# bottom_board_v6.net
KiCad netlist of a schematic drawn in EAGLE
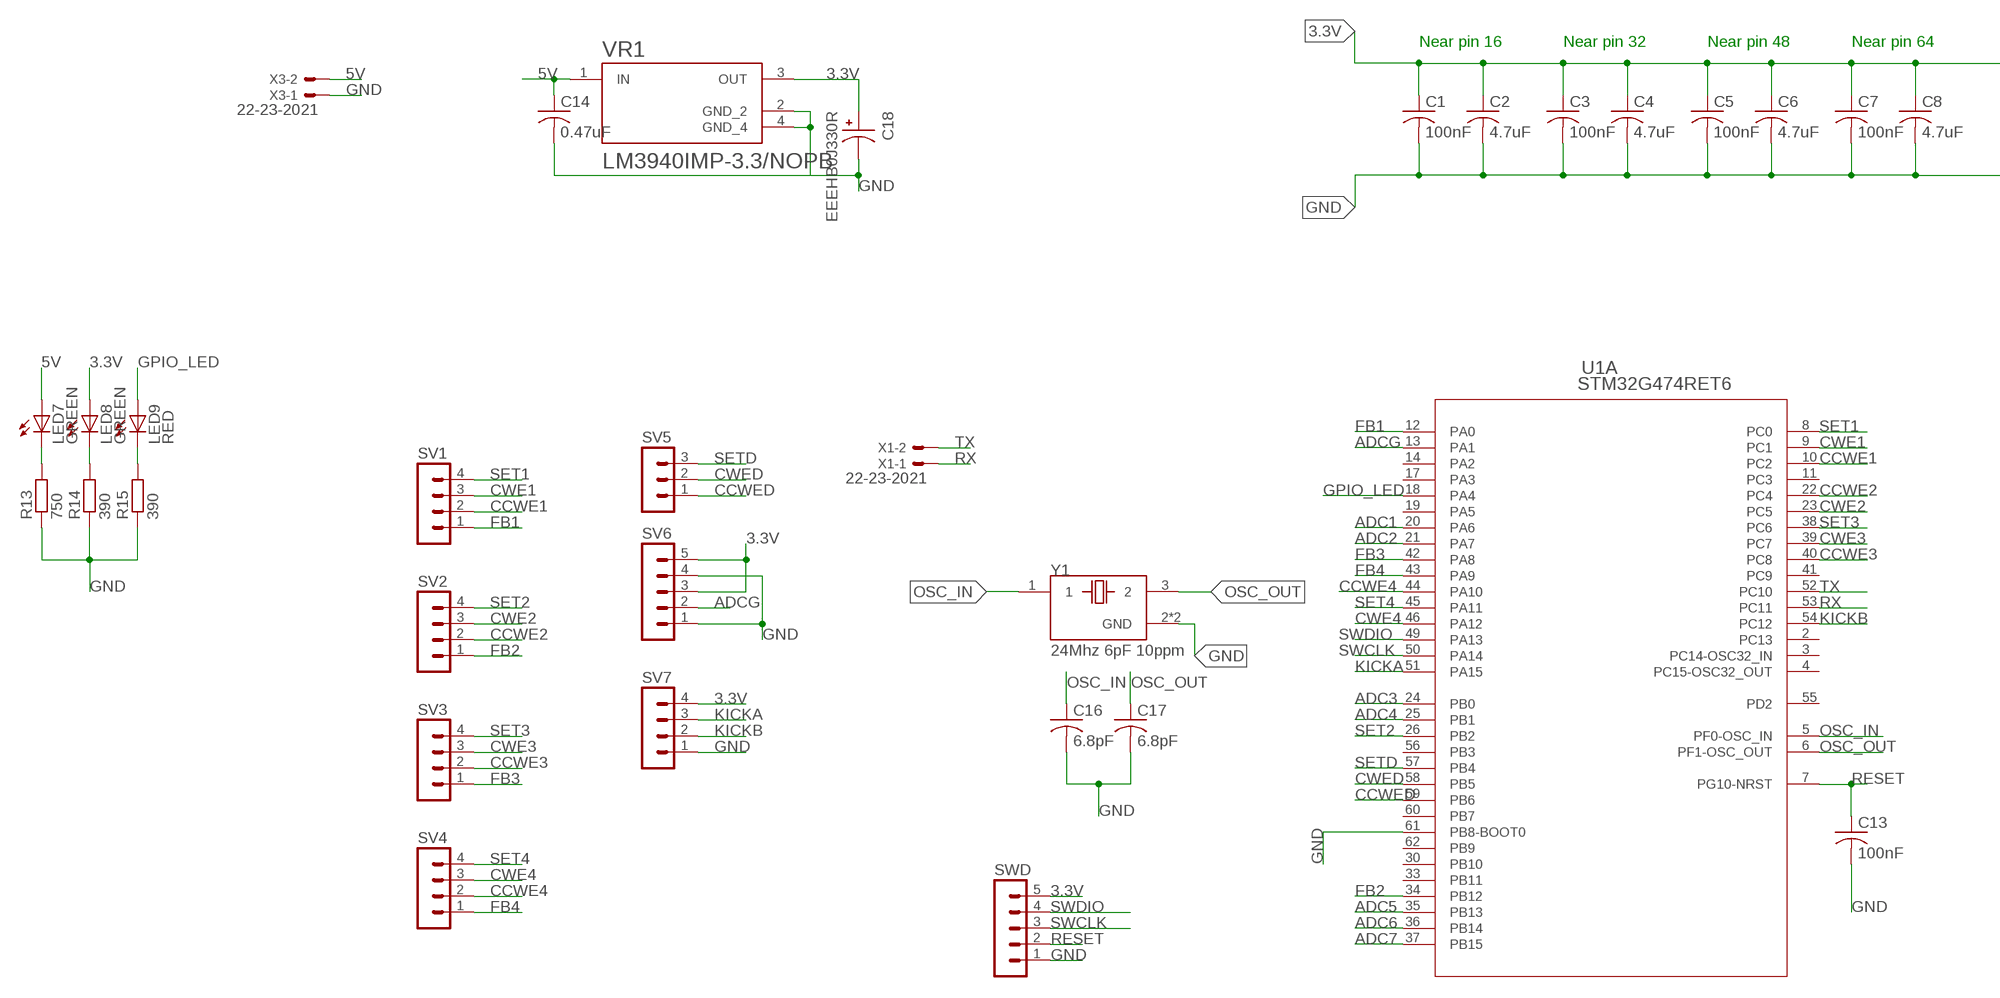
[diagram p0: schematic, sheet 1, part 1 of 2]
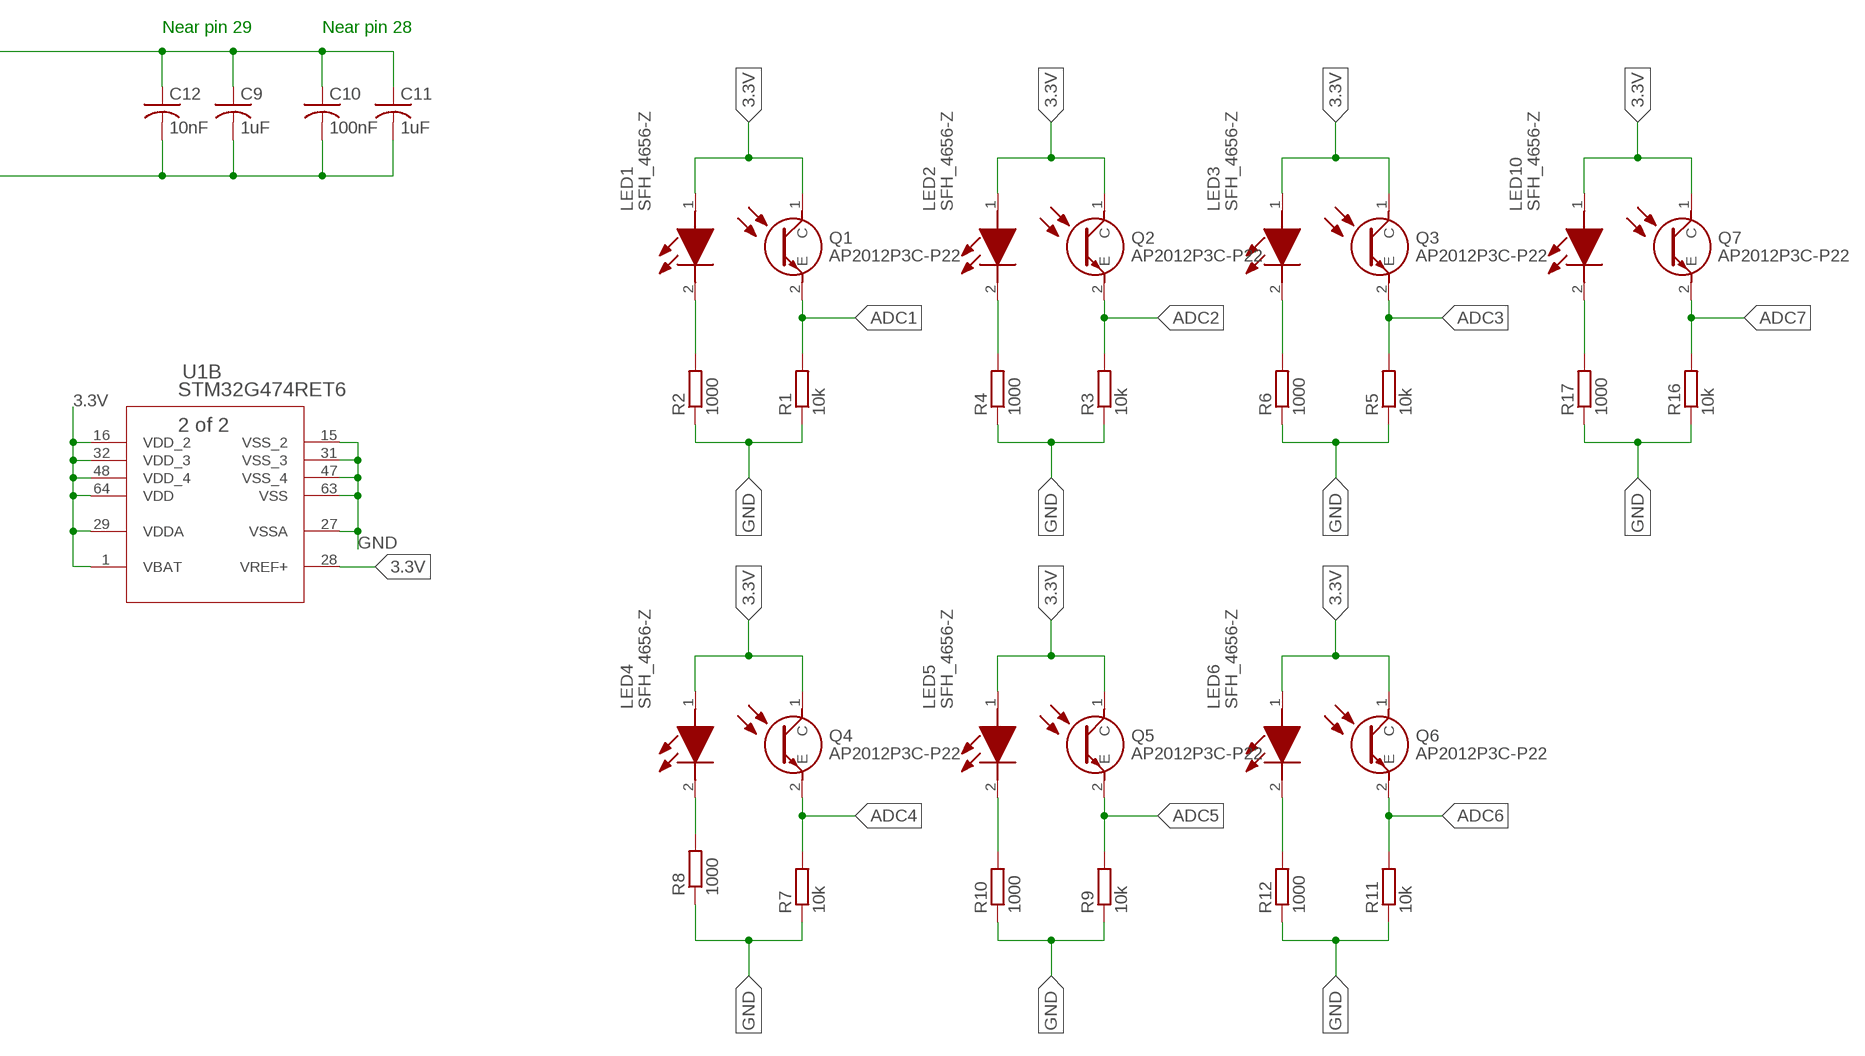
[diagram p1: schematic, sheet 1, part 2 of 2]

(export (version "E")
  (design (tool "Eeschema 10.0.6"))
  (components
    (comp (ref "C1")
      (value "100nF")
      (footprint "eagle-import:C0603")
      (libsource (lib "eagle-import") (part "C-USC0603"))
    )
    (comp (ref "C2")
      (value "4.7uF")
      (footprint "eagle-import:C0603")
      (libsource (lib "eagle-import") (part "C-USC0603"))
    )
    (comp (ref "C3")
      (value "100nF")
      (footprint "eagle-import:C0603")
      (libsource (lib "eagle-import") (part "C-USC0603"))
    )
    (comp (ref "C4")
      (value "4.7uF")
      (footprint "eagle-import:C0603")
      (libsource (lib "eagle-import") (part "C-USC0603"))
    )
    (comp (ref "C5")
      (value "100nF")
      (footprint "eagle-import:C0603")
      (libsource (lib "eagle-import") (part "C-USC0603"))
    )
    (comp (ref "C6")
      (value "4.7uF")
      (footprint "eagle-import:C0603")
      (libsource (lib "eagle-import") (part "C-USC0603"))
    )
    (comp (ref "C7")
      (value "100nF")
      (footprint "eagle-import:C0603")
      (libsource (lib "eagle-import") (part "C-USC0603"))
    )
    (comp (ref "C8")
      (value "4.7uF")
      (footprint "eagle-import:C0603")
      (libsource (lib "eagle-import") (part "C-USC0603"))
    )
    (comp (ref "C9")
      (value "1uF")
      (footprint "eagle-import:C0603")
      (libsource (lib "eagle-import") (part "C-USC0603"))
    )
    (comp (ref "C10")
      (value "100nF")
      (footprint "eagle-import:C0603")
      (libsource (lib "eagle-import") (part "C-USC0603"))
    )
    (comp (ref "C11")
      (value "1uF")
      (footprint "eagle-import:C0603")
      (libsource (lib "eagle-import") (part "C-USC0603"))
    )
    (comp (ref "C12")
      (value "10nF")
      (footprint "eagle-import:C0603")
      (libsource (lib "eagle-import") (part "C-USC0603"))
    )
    (comp (ref "C13")
      (value "100nF")
      (footprint "eagle-import:C0603")
      (libsource (lib "eagle-import") (part "C-USC0603"))
    )
    (comp (ref "C14")
      (value "0.47uF")
      (footprint "eagle-import:C0603")
      (libsource (lib "eagle-import") (part "C-USC0603"))
    )
    (comp (ref "C16")
      (value "6.8pF")
      (footprint "eagle-import:C0603")
      (libsource (lib "eagle-import") (part "C-USC0603"))
    )
    (comp (ref "C17")
      (value "6.8pF")
      (footprint "eagle-import:C0603")
      (libsource (lib "eagle-import") (part "C-USC0603"))
    )
    (comp (ref "C18")
      (value "EEEHB0J330R")
      (footprint "eagle-import:CAP_EEEHB0J330R")
      (fields (field (name "MF") "Panasonic") (field (name "MP") "EEE-HB0J330R"))
      (libsource (lib "eagle-import") (part "EEEHB0J330R"))
    )
    (comp (ref "LED1")
      (value "SFH_4656-Z")
      (footprint "eagle-import:SFH4656Z")
      (fields
        (field (name "MANUFACTURER_PART_NUMBER") "SFH 4656-Z")
        (field (name "MOUSER_PART_NUMBER") "720-SFH4656-Z")
      )
      (libsource (lib "eagle-import") (part "SFH_4656-Z"))
    )
    (comp (ref "LED2")
      (value "SFH_4656-Z")
      (footprint "eagle-import:SFH4656Z")
      (fields
        (field (name "MANUFACTURER_PART_NUMBER") "SFH 4656-Z")
        (field (name "MOUSER_PART_NUMBER") "720-SFH4656-Z")
      )
      (libsource (lib "eagle-import") (part "SFH_4656-Z"))
    )
    (comp (ref "LED3")
      (value "SFH_4656-Z")
      (footprint "eagle-import:SFH4656Z")
      (fields
        (field (name "MANUFACTURER_PART_NUMBER") "SFH 4656-Z")
        (field (name "MOUSER_PART_NUMBER") "720-SFH4656-Z")
      )
      (libsource (lib "eagle-import") (part "SFH_4656-Z"))
    )
    (comp (ref "LED4")
      (value "SFH_4656-Z")
      (footprint "eagle-import:SFH4656Z")
      (fields
        (field (name "MANUFACTURER_PART_NUMBER") "SFH 4656-Z")
        (field (name "MOUSER_PART_NUMBER") "720-SFH4656-Z")
      )
      (libsource (lib "eagle-import") (part "SFH_4656-Z"))
    )
    (comp (ref "LED5")
      (value "SFH_4656-Z")
      (footprint "eagle-import:SFH4656Z")
      (fields
        (field (name "MANUFACTURER_PART_NUMBER") "SFH 4656-Z")
        (field (name "MOUSER_PART_NUMBER") "720-SFH4656-Z")
      )
      (libsource (lib "eagle-import") (part "SFH_4656-Z"))
    )
    (comp (ref "LED6")
      (value "SFH_4656-Z")
      (footprint "eagle-import:SFH4656Z")
      (fields
        (field (name "MANUFACTURER_PART_NUMBER") "SFH 4656-Z")
        (field (name "MOUSER_PART_NUMBER") "720-SFH4656-Z")
      )
      (libsource (lib "eagle-import") (part "SFH_4656-Z"))
    )
    (comp (ref "LED7")
      (value "GREEN")
      (footprint "eagle-import:CHIPLED_0603")
      (libsource (lib "eagle-import") (part "LEDCHIPLED_0603"))
    )
    (comp (ref "LED8")
      (value "GREEN")
      (footprint "eagle-import:CHIPLED_0603")
      (libsource (lib "eagle-import") (part "LEDCHIPLED_0603"))
    )
    (comp (ref "LED9")
      (value "RED")
      (footprint "eagle-import:CHIPLED_0603")
      (libsource (lib "eagle-import") (part "LEDCHIPLED_0603"))
    )
    (comp (ref "LED10")
      (value "SFH_4656-Z")
      (footprint "eagle-import:SFH4656Z")
      (fields
        (field (name "MANUFACTURER_PART_NUMBER") "SFH 4656-Z")
        (field (name "MOUSER_PART_NUMBER") "720-SFH4656-Z")
      )
      (libsource (lib "eagle-import") (part "SFH_4656-Z"))
    )
    (comp (ref "Q1")
      (value "AP2012P3C-P22")
      (footprint "eagle-import:AP2012P3CP22")
      (fields (field (name "MOUSER_PART_NUMBER") "604-AP2012P3C-P22"))
      (libsource (lib "eagle-import") (part "AP2012P3C-P22"))
    )
    (comp (ref "Q2")
      (value "AP2012P3C-P22")
      (footprint "eagle-import:AP2012P3CP22")
      (fields (field (name "MOUSER_PART_NUMBER") "604-AP2012P3C-P22"))
      (libsource (lib "eagle-import") (part "AP2012P3C-P22"))
    )
    (comp (ref "Q3")
      (value "AP2012P3C-P22")
      (footprint "eagle-import:AP2012P3CP22")
      (fields (field (name "MOUSER_PART_NUMBER") "604-AP2012P3C-P22"))
      (libsource (lib "eagle-import") (part "AP2012P3C-P22"))
    )
    (comp (ref "Q4")
      (value "AP2012P3C-P22")
      (footprint "eagle-import:AP2012P3CP22")
      (fields (field (name "MOUSER_PART_NUMBER") "604-AP2012P3C-P22"))
      (libsource (lib "eagle-import") (part "AP2012P3C-P22"))
    )
    (comp (ref "Q5")
      (value "AP2012P3C-P22")
      (footprint "eagle-import:AP2012P3CP22")
      (fields (field (name "MOUSER_PART_NUMBER") "604-AP2012P3C-P22"))
      (libsource (lib "eagle-import") (part "AP2012P3C-P22"))
    )
    (comp (ref "Q6")
      (value "AP2012P3C-P22")
      (footprint "eagle-import:AP2012P3CP22")
      (fields (field (name "MOUSER_PART_NUMBER") "604-AP2012P3C-P22"))
      (libsource (lib "eagle-import") (part "AP2012P3C-P22"))
    )
    (comp (ref "Q7")
      (value "AP2012P3C-P22")
      (footprint "eagle-import:AP2012P3CP22")
      (fields (field (name "MOUSER_PART_NUMBER") "604-AP2012P3C-P22"))
      (libsource (lib "eagle-import") (part "AP2012P3C-P22"))
    )
    (comp (ref "R1")
      (value "10k")
      (footprint "eagle-import:R0603")
      (libsource (lib "eagle-import") (part "R-EU_R0603"))
    )
    (comp (ref "R2")
      (value "1000")
      (footprint "eagle-import:R0603")
      (libsource (lib "eagle-import") (part "R-EU_R0603"))
    )
    (comp (ref "R3")
      (value "10k")
      (footprint "eagle-import:R0603")
      (libsource (lib "eagle-import") (part "R-EU_R0603"))
    )
    (comp (ref "R4")
      (value "1000")
      (footprint "eagle-import:R0603")
      (libsource (lib "eagle-import") (part "R-EU_R0603"))
    )
    (comp (ref "R5")
      (value "10k")
      (footprint "eagle-import:R0603")
      (libsource (lib "eagle-import") (part "R-EU_R0603"))
    )
    (comp (ref "R6")
      (value "1000")
      (footprint "eagle-import:R0603")
      (libsource (lib "eagle-import") (part "R-EU_R0603"))
    )
    (comp (ref "R7")
      (value "10k")
      (footprint "eagle-import:R0603")
      (libsource (lib "eagle-import") (part "R-EU_R0603"))
    )
    (comp (ref "R8")
      (value "1000")
      (footprint "eagle-import:R0603")
      (libsource (lib "eagle-import") (part "R-EU_R0603"))
    )
    (comp (ref "R9")
      (value "10k")
      (footprint "eagle-import:R0603")
      (fields (field (name "POPULARITY") "10k"))
      (libsource (lib "eagle-import") (part "R-EU_R0603"))
    )
    (comp (ref "R10")
      (value "1000")
      (footprint "eagle-import:R0603")
      (libsource (lib "eagle-import") (part "R-EU_R0603"))
    )
    (comp (ref "R11")
      (value "10k")
      (footprint "eagle-import:R0603")
      (libsource (lib "eagle-import") (part "R-EU_R0603"))
    )
    (comp (ref "R12")
      (value "1000")
      (footprint "eagle-import:R0603")
      (libsource (lib "eagle-import") (part "R-EU_R0603"))
    )
    (comp (ref "R13")
      (value "750")
      (footprint "eagle-import:R0603")
      (libsource (lib "eagle-import") (part "R-EU_R0603"))
    )
    (comp (ref "R14")
      (value "390")
      (footprint "eagle-import:R0603")
      (libsource (lib "eagle-import") (part "R-EU_R0603"))
    )
    (comp (ref "R15")
      (value "390")
      (footprint "eagle-import:R0603")
      (libsource (lib "eagle-import") (part "R-EU_R0603"))
    )
    (comp (ref "R16")
      (value "10k")
      (footprint "eagle-import:R0603")
      (libsource (lib "eagle-import") (part "R-EU_R0603"))
    )
    (comp (ref "R17")
      (value "1000")
      (footprint "eagle-import:R0603")
      (libsource (lib "eagle-import") (part "R-EU_R0603"))
    )
    (comp (ref "SV1")
      (value "MA04-1")
      (footprint "eagle-import:MA04-1")
      (libsource (lib "eagle-import") (part "MA04-1"))
    )
    (comp (ref "SV2")
      (value "MA04-1")
      (footprint "eagle-import:MA04-1")
      (libsource (lib "eagle-import") (part "MA04-1"))
    )
    (comp (ref "SV3")
      (value "MA04-1")
      (footprint "eagle-import:MA04-1")
      (libsource (lib "eagle-import") (part "MA04-1"))
    )
    (comp (ref "SV4")
      (value "MA04-1")
      (footprint "eagle-import:MA04-1")
      (libsource (lib "eagle-import") (part "MA04-1"))
    )
    (comp (ref "SV5")
      (value "MA03-1")
      (footprint "eagle-import:MA03-1")
      (libsource (lib "eagle-import") (part "MA03-1"))
    )
    (comp (ref "SV6")
      (value "MA05-1")
      (footprint "eagle-import:MA05-1")
      (libsource (lib "eagle-import") (part "MA05-1"))
    )
    (comp (ref "SV7")
      (value "MA04-1")
      (footprint "eagle-import:MA04-1")
      (libsource (lib "eagle-import") (part "MA04-1"))
    )
    (comp (ref "SWD")
      (value "MA05-1")
      (footprint "eagle-import:MA05-1")
      (libsource (lib "eagle-import") (part "MA05-1"))
    )
    (comp (ref "U1")
      (value "STM32G474RET6")
      (footprint "eagle-import:LQFP64-10X10MM")
      (fields (field (name "COPYRIGHT") "Copyright (C) 2023 Ultra Librarian. All rights reserved."))
      (libsource (lib "eagle-import") (part "STM32G474RET6"))
    )
    (comp (ref "VR1")
      (value "LM3940IMP-3.3/NOPB")
      (footprint "eagle-import:VREG_LM3940IMP-3.3_NOPB")
      (fields (field (name "MF") "Texas Instruments") (field (name "MP") "LM3940IMP-3.3"))
      (libsource (lib "eagle-import") (part "LM3940IMP-3.3/NOPB"))
    )
    (comp (ref "X1")
      (value "22-23-2021")
      (footprint "eagle-import:22-23-2021")
      (fields (field (name "MF") "MOLEX"))
      (libsource (lib "eagle-import") (part "22-23-2021"))
    )
    (comp (ref "X3")
      (value "22-23-2021")
      (footprint "eagle-import:22-23-2021")
      (fields (field (name "MF") "MOLEX"))
      (libsource (lib "eagle-import") (part "22-23-2021"))
    )
    (comp (ref "Y1")
      (value "24Mhz 6pF 10ppm")
      (footprint "eagle-import:XTAL_TSX-3225_16.0000MF18X-AC3")
      (fields (field (name "MF") "EPSON") (field (name "MP") "TSX-3225 16.0000MF18X-AC3"))
      (libsource (lib "eagle-import") (part "TSX-3225_16.0000MF18X-AC3"))
    )
  )
  (nets
    (net (code "1") (name "/5V") (class "Default")
      (node (ref "C14") (pin "1") (pinfunction "1_1") (pintype "passive"))
      (node (ref "LED7") (pin "A") (pinfunction "A_A") (pintype "passive"))
      (node (ref "VR1") (pin "1") (pinfunction "IN_1") (pintype "input"))
      (node (ref "X3") (pin "2") (pinfunction "S_2") (pintype "passive"))
    )
    (net (code "2") (name "/ADCG") (class "Default")
      (node (ref "SV6") (pin "2") (pinfunction "2_2") (pintype "passive"))
      (node (ref "U1") (pin "13") (pinfunction "PA1_13") (pintype "bidirectional"))
    )
    (net (code "3") (name "/CCWE1") (class "Default")
      (node (ref "SV1") (pin "2") (pinfunction "2_2") (pintype "passive"))
      (node (ref "U1") (pin "10") (pinfunction "PC2_10") (pintype "bidirectional"))
    )
    (net (code "4") (name "/CCWE2") (class "Default")
      (node (ref "SV2") (pin "2") (pinfunction "2_2") (pintype "passive"))
      (node (ref "U1") (pin "22") (pinfunction "PC4_22") (pintype "bidirectional"))
    )
    (net (code "5") (name "/CCWE3") (class "Default")
      (node (ref "SV3") (pin "2") (pinfunction "2_2") (pintype "passive"))
      (node (ref "U1") (pin "40") (pinfunction "PC8_40") (pintype "bidirectional"))
    )
    (net (code "6") (name "/CCWE4") (class "Default")
      (node (ref "SV4") (pin "2") (pinfunction "2_2") (pintype "passive"))
      (node (ref "U1") (pin "44") (pinfunction "PA10_44") (pintype "bidirectional"))
    )
    (net (code "7") (name "/CCWED") (class "Default")
      (node (ref "SV5") (pin "1") (pinfunction "1_1") (pintype "passive"))
      (node (ref "U1") (pin "59") (pinfunction "PB6_59") (pintype "bidirectional"))
    )
    (net (code "8") (name "/CWE1") (class "Default")
      (node (ref "SV1") (pin "3") (pinfunction "3_3") (pintype "passive"))
      (node (ref "U1") (pin "9") (pinfunction "PC1_9") (pintype "bidirectional"))
    )
    (net (code "9") (name "/CWE2") (class "Default")
      (node (ref "SV2") (pin "3") (pinfunction "3_3") (pintype "passive"))
      (node (ref "U1") (pin "23") (pinfunction "PC5_23") (pintype "bidirectional"))
    )
    (net (code "10") (name "/CWE3") (class "Default")
      (node (ref "SV3") (pin "3") (pinfunction "3_3") (pintype "passive"))
      (node (ref "U1") (pin "39") (pinfunction "PC7_39") (pintype "bidirectional"))
    )
    (net (code "11") (name "/CWE4") (class "Default")
      (node (ref "SV4") (pin "3") (pinfunction "3_3") (pintype "passive"))
      (node (ref "U1") (pin "46") (pinfunction "PA12_46") (pintype "bidirectional"))
    )
    (net (code "12") (name "/CWED") (class "Default")
      (node (ref "SV5") (pin "2") (pinfunction "2_2") (pintype "passive"))
      (node (ref "U1") (pin "58") (pinfunction "PB5_58") (pintype "bidirectional"))
    )
    (net (code "13") (name "/FB1") (class "Default")
      (node (ref "SV1") (pin "1") (pinfunction "1_1") (pintype "passive"))
      (node (ref "U1") (pin "12") (pinfunction "PA0_12") (pintype "bidirectional"))
    )
    (net (code "14") (name "/FB2") (class "Default")
      (node (ref "SV2") (pin "1") (pinfunction "1_1") (pintype "passive"))
      (node (ref "U1") (pin "34") (pinfunction "PB12_34") (pintype "bidirectional"))
    )
    (net (code "15") (name "/FB3") (class "Default")
      (node (ref "SV3") (pin "1") (pinfunction "1_1") (pintype "passive"))
      (node (ref "U1") (pin "42") (pinfunction "PA8_42") (pintype "bidirectional"))
    )
    (net (code "16") (name "/FB4") (class "Default")
      (node (ref "SV4") (pin "1") (pinfunction "1_1") (pintype "passive"))
      (node (ref "U1") (pin "43") (pinfunction "PA9_43") (pintype "bidirectional"))
    )
    (net (code "17") (name "/GPIO_LED") (class "Default")
      (node (ref "LED9") (pin "A") (pinfunction "A_A") (pintype "passive"))
      (node (ref "U1") (pin "18") (pinfunction "PA4_18") (pintype "bidirectional"))
    )
    (net (code "18") (name "/KICKA") (class "Default")
      (node (ref "SV7") (pin "3") (pinfunction "3_3") (pintype "passive"))
      (node (ref "U1") (pin "51") (pinfunction "PA15_51") (pintype "bidirectional"))
    )
    (net (code "19") (name "/KICKB") (class "Default")
      (node (ref "SV7") (pin "2") (pinfunction "2_2") (pintype "passive"))
      (node (ref "U1") (pin "54") (pinfunction "PC12_54") (pintype "bidirectional"))
    )
    (net (code "20") (name "/RESET") (class "Default")
      (node (ref "C13") (pin "1") (pinfunction "1_1") (pintype "passive"))
      (node (ref "SWD") (pin "2") (pinfunction "2_2") (pintype "passive"))
      (node (ref "U1") (pin "7") (pinfunction "PG10-NRST_7") (pintype "bidirectional"))
    )
    (net (code "21") (name "/RX") (class "Default")
      (node (ref "U1") (pin "53") (pinfunction "PC11_53") (pintype "bidirectional"))
      (node (ref "X1") (pin "1") (pinfunction "S_1") (pintype "passive"))
    )
    (net (code "22") (name "/SET1") (class "Default")
      (node (ref "SV1") (pin "4") (pinfunction "4_4") (pintype "passive"))
      (node (ref "U1") (pin "8") (pinfunction "PC0_8") (pintype "bidirectional"))
    )
    (net (code "23") (name "/SET2") (class "Default")
      (node (ref "SV2") (pin "4") (pinfunction "4_4") (pintype "passive"))
      (node (ref "U1") (pin "26") (pinfunction "PB2_26") (pintype "bidirectional"))
    )
    (net (code "24") (name "/SET3") (class "Default")
      (node (ref "SV3") (pin "4") (pinfunction "4_4") (pintype "passive"))
      (node (ref "U1") (pin "38") (pinfunction "PC6_38") (pintype "bidirectional"))
    )
    (net (code "25") (name "/SET4") (class "Default")
      (node (ref "SV4") (pin "4") (pinfunction "4_4") (pintype "passive"))
      (node (ref "U1") (pin "45") (pinfunction "PA11_45") (pintype "bidirectional"))
    )
    (net (code "26") (name "/SETD") (class "Default")
      (node (ref "SV5") (pin "3") (pinfunction "3_3") (pintype "passive"))
      (node (ref "U1") (pin "57") (pinfunction "PB4_57") (pintype "bidirectional"))
    )
    (net (code "27") (name "/SWCLK") (class "Default")
      (node (ref "SWD") (pin "3") (pinfunction "3_3") (pintype "passive"))
      (node (ref "U1") (pin "50") (pinfunction "PA14_50") (pintype "bidirectional"))
    )
    (net (code "28") (name "/SWDIO") (class "Default")
      (node (ref "SWD") (pin "4") (pinfunction "4_4") (pintype "passive"))
      (node (ref "U1") (pin "49") (pinfunction "PA13_49") (pintype "bidirectional"))
    )
    (net (code "29") (name "/TX") (class "Default")
      (node (ref "U1") (pin "52") (pinfunction "PC10_52") (pintype "bidirectional"))
      (node (ref "X1") (pin "2") (pinfunction "S_2") (pintype "passive"))
    )
    (net (code "30") (name "3.3V") (class "Default")
      (node (ref "C1") (pin "1") (pinfunction "1_1") (pintype "passive"))
      (node (ref "C10") (pin "1") (pinfunction "1_1") (pintype "passive"))
      (node (ref "C11") (pin "1") (pinfunction "1_1") (pintype "passive"))
      (node (ref "C12") (pin "1") (pinfunction "1_1") (pintype "passive"))
      (node (ref "C18") (pin "1") (pinfunction "1_1") (pintype "passive"))
      (node (ref "C2") (pin "1") (pinfunction "1_1") (pintype "passive"))
      (node (ref "C3") (pin "1") (pinfunction "1_1") (pintype "passive"))
      (node (ref "C4") (pin "1") (pinfunction "1_1") (pintype "passive"))
      (node (ref "C5") (pin "1") (pinfunction "1_1") (pintype "passive"))
      (node (ref "C6") (pin "1") (pinfunction "1_1") (pintype "passive"))
      (node (ref "C7") (pin "1") (pinfunction "1_1") (pintype "passive"))
      (node (ref "C8") (pin "1") (pinfunction "1_1") (pintype "passive"))
      (node (ref "C9") (pin "1") (pinfunction "1_1") (pintype "passive"))
      (node (ref "LED1") (pin "1") (pinfunction "A_1") (pintype "bidirectional"))
      (node (ref "LED10") (pin "1") (pinfunction "A_1") (pintype "bidirectional"))
      (node (ref "LED2") (pin "1") (pinfunction "A_1") (pintype "bidirectional"))
      (node (ref "LED3") (pin "1") (pinfunction "A_1") (pintype "bidirectional"))
      (node (ref "LED4") (pin "1") (pinfunction "A_1") (pintype "bidirectional"))
      (node (ref "LED5") (pin "1") (pinfunction "A_1") (pintype "bidirectional"))
      (node (ref "LED6") (pin "1") (pinfunction "A_1") (pintype "bidirectional"))
      (node (ref "LED8") (pin "A") (pinfunction "A_A") (pintype "passive"))
      (node (ref "Q1") (pin "1") (pinfunction "C_1") (pintype "bidirectional"))
      (node (ref "Q2") (pin "1") (pinfunction "C_1") (pintype "bidirectional"))
      (node (ref "Q3") (pin "1") (pinfunction "C_1") (pintype "bidirectional"))
      (node (ref "Q4") (pin "1") (pinfunction "C_1") (pintype "bidirectional"))
      (node (ref "Q5") (pin "1") (pinfunction "C_1") (pintype "bidirectional"))
      (node (ref "Q6") (pin "1") (pinfunction "C_1") (pintype "bidirectional"))
      (node (ref "Q7") (pin "1") (pinfunction "C_1") (pintype "bidirectional"))
      (node (ref "SV6") (pin "3") (pinfunction "3_3") (pintype "passive"))
      (node (ref "SV6") (pin "5") (pinfunction "5_5") (pintype "passive"))
      (node (ref "SV7") (pin "4") (pinfunction "4_4") (pintype "passive"))
      (node (ref "SWD") (pin "5") (pinfunction "5_5") (pintype "passive"))
      (node (ref "U1") (pin "1") (pinfunction "VBAT_1") (pintype "power_in"))
      (node (ref "U1") (pin "16") (pinfunction "VDD_2_16") (pintype "power_in"))
      (node (ref "U1") (pin "28") (pinfunction "VREF+_28") (pintype "power_in"))
      (node (ref "U1") (pin "29") (pinfunction "VDDA_29") (pintype "power_in"))
      (node (ref "U1") (pin "32") (pinfunction "VDD_3_32") (pintype "power_in"))
      (node (ref "U1") (pin "48") (pinfunction "VDD_4_48") (pintype "power_in"))
      (node (ref "U1") (pin "64") (pinfunction "VDD_64") (pintype "power_in"))
      (node (ref "VR1") (pin "3") (pinfunction "OUT_3") (pintype "output"))
    )
    (net (code "31") (name "ADC1") (class "Default")
      (node (ref "Q1") (pin "2") (pinfunction "E_2") (pintype "bidirectional"))
      (node (ref "R1") (pin "2") (pinfunction "2_2") (pintype "passive"))
      (node (ref "U1") (pin "20") (pinfunction "PA6_20") (pintype "bidirectional"))
    )
    (net (code "32") (name "ADC2") (class "Default")
      (node (ref "Q2") (pin "2") (pinfunction "E_2") (pintype "bidirectional"))
      (node (ref "R3") (pin "2") (pinfunction "2_2") (pintype "passive"))
      (node (ref "U1") (pin "21") (pinfunction "PA7_21") (pintype "bidirectional"))
    )
    (net (code "33") (name "ADC3") (class "Default")
      (node (ref "Q3") (pin "2") (pinfunction "E_2") (pintype "bidirectional"))
      (node (ref "R5") (pin "2") (pinfunction "2_2") (pintype "passive"))
      (node (ref "U1") (pin "24") (pinfunction "PB0_24") (pintype "bidirectional"))
    )
    (net (code "34") (name "ADC4") (class "Default")
      (node (ref "Q4") (pin "2") (pinfunction "E_2") (pintype "bidirectional"))
      (node (ref "R7") (pin "2") (pinfunction "2_2") (pintype "passive"))
      (node (ref "U1") (pin "25") (pinfunction "PB1_25") (pintype "bidirectional"))
    )
    (net (code "35") (name "ADC5") (class "Default")
      (node (ref "Q5") (pin "2") (pinfunction "E_2") (pintype "bidirectional"))
      (node (ref "R9") (pin "2") (pinfunction "2_2") (pintype "passive"))
      (node (ref "U1") (pin "35") (pinfunction "PB13_35") (pintype "bidirectional"))
    )
    (net (code "36") (name "ADC6") (class "Default")
      (node (ref "Q6") (pin "2") (pinfunction "E_2") (pintype "bidirectional"))
      (node (ref "R11") (pin "2") (pinfunction "2_2") (pintype "passive"))
      (node (ref "U1") (pin "36") (pinfunction "PB14_36") (pintype "bidirectional"))
    )
    (net (code "37") (name "ADC7") (class "Default")
      (node (ref "Q7") (pin "2") (pinfunction "E_2") (pintype "bidirectional"))
      (node (ref "R16") (pin "2") (pinfunction "2_2") (pintype "passive"))
      (node (ref "U1") (pin "37") (pinfunction "PB15_37") (pintype "bidirectional"))
    )
    (net (code "38") (name "GND") (class "Default")
      (node (ref "C1") (pin "2") (pinfunction "2_2") (pintype "passive"))
      (node (ref "C10") (pin "2") (pinfunction "2_2") (pintype "passive"))
      (node (ref "C11") (pin "2") (pinfunction "2_2") (pintype "passive"))
      (node (ref "C12") (pin "2") (pinfunction "2_2") (pintype "passive"))
      (node (ref "C13") (pin "2") (pinfunction "2_2") (pintype "passive"))
      (node (ref "C14") (pin "2") (pinfunction "2_2") (pintype "passive"))
      (node (ref "C16") (pin "2") (pinfunction "2_2") (pintype "passive"))
      (node (ref "C17") (pin "2") (pinfunction "2_2") (pintype "passive"))
      (node (ref "C18") (pin "2") (pinfunction "2_2") (pintype "passive"))
      (node (ref "C2") (pin "2") (pinfunction "2_2") (pintype "passive"))
      (node (ref "C3") (pin "2") (pinfunction "2_2") (pintype "passive"))
      (node (ref "C4") (pin "2") (pinfunction "2_2") (pintype "passive"))
      (node (ref "C5") (pin "2") (pinfunction "2_2") (pintype "passive"))
      (node (ref "C6") (pin "2") (pinfunction "2_2") (pintype "passive"))
      (node (ref "C7") (pin "2") (pinfunction "2_2") (pintype "passive"))
      (node (ref "C8") (pin "2") (pinfunction "2_2") (pintype "passive"))
      (node (ref "C9") (pin "2") (pinfunction "2_2") (pintype "passive"))
      (node (ref "R1") (pin "1") (pinfunction "1_1") (pintype "passive"))
      (node (ref "R10") (pin "1") (pinfunction "1_1") (pintype "passive"))
      (node (ref "R11") (pin "1") (pinfunction "1_1") (pintype "passive"))
      (node (ref "R12") (pin "1") (pinfunction "1_1") (pintype "passive"))
      (node (ref "R13") (pin "1") (pinfunction "1_1") (pintype "passive"))
      (node (ref "R14") (pin "1") (pinfunction "1_1") (pintype "passive"))
      (node (ref "R15") (pin "1") (pinfunction "1_1") (pintype "passive"))
      (node (ref "R16") (pin "1") (pinfunction "1_1") (pintype "passive"))
      (node (ref "R17") (pin "1") (pinfunction "1_1") (pintype "passive"))
      (node (ref "R2") (pin "1") (pinfunction "1_1") (pintype "passive"))
      (node (ref "R3") (pin "1") (pinfunction "1_1") (pintype "passive"))
      (node (ref "R4") (pin "1") (pinfunction "1_1") (pintype "passive"))
      (node (ref "R5") (pin "1") (pinfunction "1_1") (pintype "passive"))
      (node (ref "R6") (pin "1") (pinfunction "1_1") (pintype "passive"))
      (node (ref "R7") (pin "1") (pinfunction "1_1") (pintype "passive"))
      (node (ref "R8") (pin "1") (pinfunction "1_1") (pintype "passive"))
      (node (ref "R9") (pin "1") (pinfunction "1_1") (pintype "passive"))
      (node (ref "SV6") (pin "1") (pinfunction "1_1") (pintype "passive"))
      (node (ref "SV6") (pin "4") (pinfunction "4_4") (pintype "passive"))
      (node (ref "SV7") (pin "1") (pinfunction "1_1") (pintype "passive"))
      (node (ref "SWD") (pin "1") (pinfunction "1_1") (pintype "passive"))
      (node (ref "U1") (pin "15") (pinfunction "VSS_2_15") (pintype "power_in"))
      (node (ref "U1") (pin "27") (pinfunction "VSSA_27") (pintype "power_in"))
      (node (ref "U1") (pin "31") (pinfunction "VSS_3_31") (pintype "power_in"))
      (node (ref "U1") (pin "47") (pinfunction "VSS_4_47") (pintype "power_in"))
      (node (ref "U1") (pin "61") (pinfunction "PB8-BOOT0_61") (pintype "bidirectional"))
      (node (ref "U1") (pin "63") (pinfunction "VSS_63") (pintype "power_in"))
      (node (ref "VR1") (pin "2") (pinfunction "GND_2_2") (pintype "power_in"))
      (node (ref "VR1") (pin "4") (pinfunction "GND_4_4") (pintype "power_in"))
      (node (ref "X3") (pin "1") (pinfunction "S_1") (pintype "passive"))
      (node (ref "Y1") (pin "2") (pinfunction "GND_2") (pintype "power_in"))
      (node (ref "Y1") (pin "4") (pinfunction "GND_4") (pintype "power_in"))
    )
    (net (code "39") (name "Net-(LED1-K)") (class "Default")
      (node (ref "LED1") (pin "2") (pinfunction "K_2") (pintype "bidirectional"))
      (node (ref "R2") (pin "2") (pinfunction "2_2") (pintype "passive"))
    )
    (net (code "40") (name "Net-(LED2-K)") (class "Default")
      (node (ref "LED2") (pin "2") (pinfunction "K_2") (pintype "bidirectional"))
      (node (ref "R4") (pin "2") (pinfunction "2_2") (pintype "passive"))
    )
    (net (code "41") (name "Net-(LED3-K)") (class "Default")
      (node (ref "LED3") (pin "2") (pinfunction "K_2") (pintype "bidirectional"))
      (node (ref "R6") (pin "2") (pinfunction "2_2") (pintype "passive"))
    )
    (net (code "42") (name "Net-(LED4-K)") (class "Default")
      (node (ref "LED4") (pin "2") (pinfunction "K_2") (pintype "bidirectional"))
      (node (ref "R8") (pin "2") (pinfunction "2_2") (pintype "passive"))
    )
    (net (code "43") (name "Net-(LED5-K)") (class "Default")
      (node (ref "LED5") (pin "2") (pinfunction "K_2") (pintype "bidirectional"))
      (node (ref "R10") (pin "2") (pinfunction "2_2") (pintype "passive"))
    )
    (net (code "44") (name "Net-(LED6-K)") (class "Default")
      (node (ref "LED6") (pin "2") (pinfunction "K_2") (pintype "bidirectional"))
      (node (ref "R12") (pin "2") (pinfunction "2_2") (pintype "passive"))
    )
    (net (code "45") (name "Net-(LED7-PadC)") (class "Default")
      (node (ref "LED7") (pin "C") (pinfunction "C_C") (pintype "passive"))
      (node (ref "R13") (pin "2") (pinfunction "2_2") (pintype "passive"))
    )
    (net (code "46") (name "Net-(LED8-PadC)") (class "Default")
      (node (ref "LED8") (pin "C") (pinfunction "C_C") (pintype "passive"))
      (node (ref "R14") (pin "2") (pinfunction "2_2") (pintype "passive"))
    )
    (net (code "47") (name "Net-(LED9-PadC)") (class "Default")
      (node (ref "LED9") (pin "C") (pinfunction "C_C") (pintype "passive"))
      (node (ref "R15") (pin "2") (pinfunction "2_2") (pintype "passive"))
    )
    (net (code "48") (name "Net-(LED10-K)") (class "Default")
      (node (ref "LED10") (pin "2") (pinfunction "K_2") (pintype "bidirectional"))
      (node (ref "R17") (pin "2") (pinfunction "2_2") (pintype "passive"))
    )
    (net (code "49") (name "OSC_IN") (class "Default")
      (node (ref "C16") (pin "1") (pinfunction "1_1") (pintype "passive"))
      (node (ref "U1") (pin "5") (pinfunction "PF0-OSC_IN_5") (pintype "bidirectional"))
      (node (ref "Y1") (pin "1") (pinfunction "1_1") (pintype "passive"))
    )
    (net (code "50") (name "OSC_OUT") (class "Default")
      (node (ref "C17") (pin "1") (pinfunction "1_1") (pintype "passive"))
      (node (ref "U1") (pin "6") (pinfunction "PF1-OSC_OUT_6") (pintype "bidirectional"))
      (node (ref "Y1") (pin "3") (pinfunction "2_3") (pintype "passive"))
    )
    (net (code "51") (name "unconnected-(U1A-PA2-Pad14)") (class "Default")
      (node (ref "U1") (pin "14") (pinfunction "PA2_14") (pintype "bidirectional"))
    )
    (net (code "52") (name "unconnected-(U1A-PA3-Pad17)") (class "Default")
      (node (ref "U1") (pin "17") (pinfunction "PA3_17") (pintype "bidirectional"))
    )
    (net (code "53") (name "unconnected-(U1A-PA5-Pad19)") (class "Default")
      (node (ref "U1") (pin "19") (pinfunction "PA5_19") (pintype "bidirectional"))
    )
    (net (code "54") (name "unconnected-(U1A-PB3-Pad56)") (class "Default")
      (node (ref "U1") (pin "56") (pinfunction "PB3_56") (pintype "bidirectional"))
    )
    (net (code "55") (name "unconnected-(U1A-PB7-Pad60)") (class "Default")
      (node (ref "U1") (pin "60") (pinfunction "PB7_60") (pintype "bidirectional"))
    )
    (net (code "56") (name "unconnected-(U1A-PB9-Pad62)") (class "Default")
      (node (ref "U1") (pin "62") (pinfunction "PB9_62") (pintype "bidirectional"))
    )
    (net (code "57") (name "unconnected-(U1A-PB10-Pad30)") (class "Default")
      (node (ref "U1") (pin "30") (pinfunction "PB10_30") (pintype "bidirectional"))
    )
    (net (code "58") (name "unconnected-(U1A-PB11-Pad33)") (class "Default")
      (node (ref "U1") (pin "33") (pinfunction "PB11_33") (pintype "bidirectional"))
    )
    (net (code "59") (name "unconnected-(U1A-PC3-Pad11)") (class "Default")
      (node (ref "U1") (pin "11") (pinfunction "PC3_11") (pintype "bidirectional"))
    )
    (net (code "60") (name "unconnected-(U1A-PC9-Pad41)") (class "Default")
      (node (ref "U1") (pin "41") (pinfunction "PC9_41") (pintype "bidirectional"))
    )
    (net (code "61") (name "unconnected-(U1A-PC13-Pad2)") (class "Default")
      (node (ref "U1") (pin "2") (pinfunction "PC13_2") (pintype "bidirectional"))
    )
    (net (code "62") (name "unconnected-(U1A-PC14-OSC32_IN-Pad3)") (class "Default")
      (node (ref "U1") (pin "3") (pinfunction "PC14-OSC32_IN_3") (pintype "bidirectional"))
    )
    (net (code "63") (name "unconnected-(U1A-PC15-OSC32_OUT-Pad4)") (class "Default")
      (node (ref "U1") (pin "4") (pinfunction "PC15-OSC32_OUT_4") (pintype "bidirectional"))
    )
    (net (code "64") (name "unconnected-(U1A-PD2-Pad55)") (class "Default")
      (node (ref "U1") (pin "55") (pinfunction "PD2_55") (pintype "bidirectional"))
    )
  )
)
